# Sheet1.net
KiCad netlist of a schematic drawn in Altium Designer
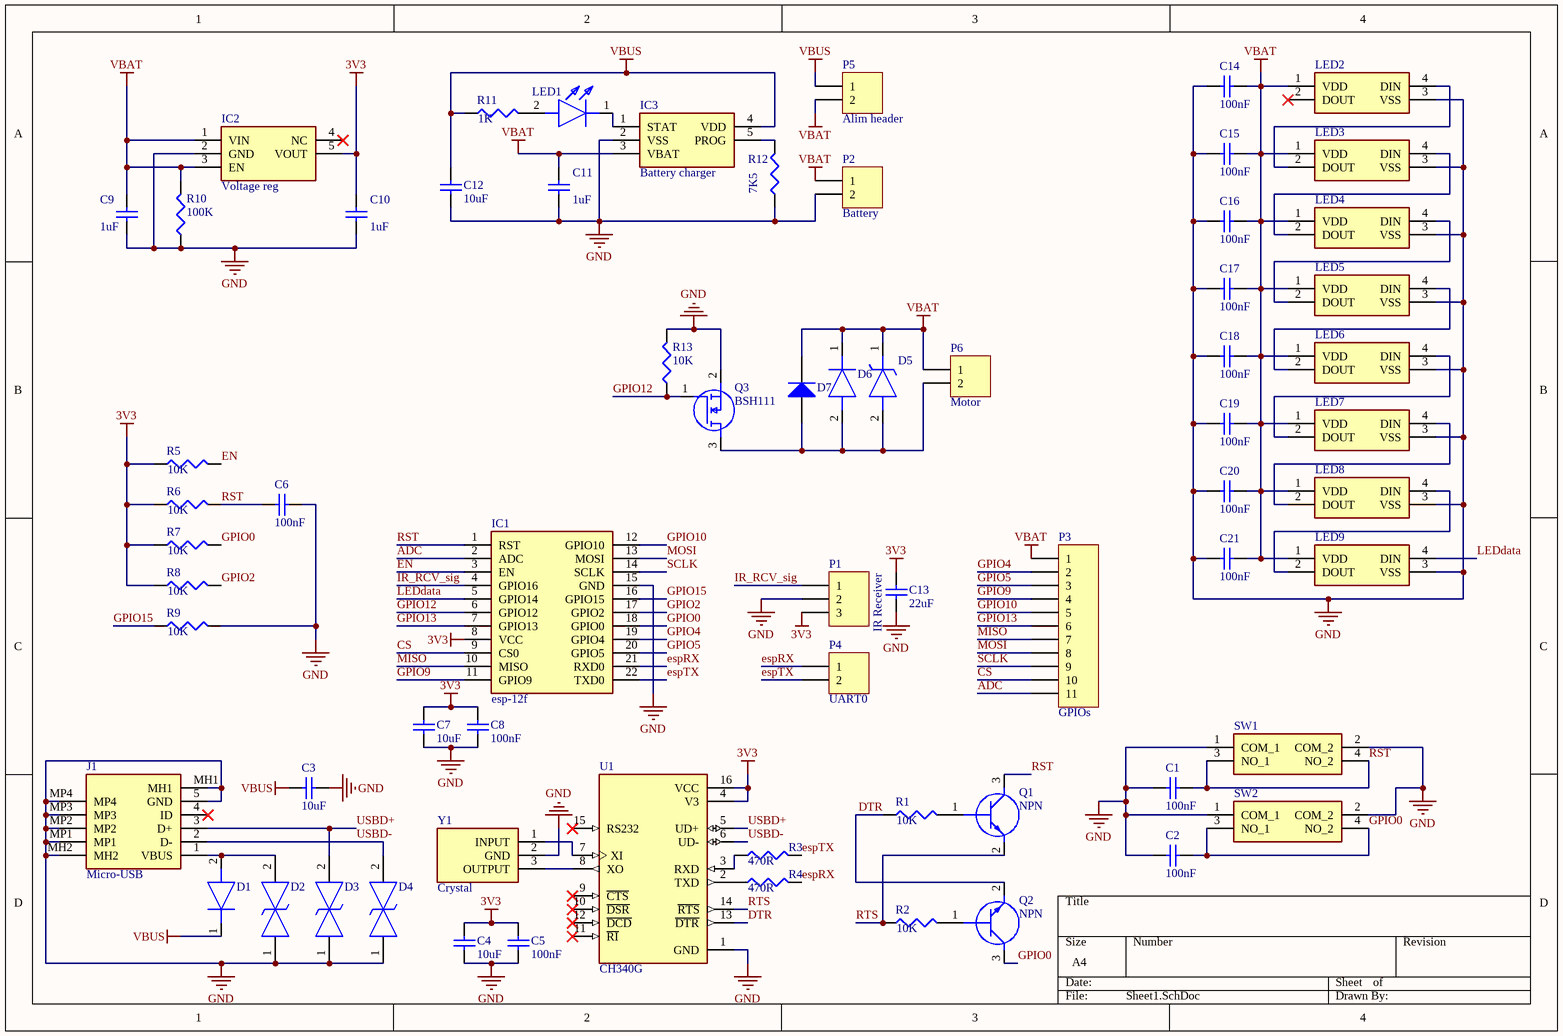
[diagram p0: Sheet1.SchDoc]

(export (version "E")
  (design (tool "Eeschema 10.0.6"))
  (components
    (comp (ref "C1")
      (value "100nF")
      (footprint "1608[0603]")
      (description "Capacitor (Semiconductor SIM Model)")
      (fields (field (name "Comment") "Cap Semi") (field (name "PUBLISHER") "Altium Limited"))
      (libsource (lib "Miscellaneous Devices") (part "Cap Semi"))
    )
    (comp (ref "C2")
      (value "100nF")
      (footprint "1608[0603]")
      (description "Capacitor (Semiconductor SIM Model)")
      (fields (field (name "Comment") "Cap Semi") (field (name "PUBLISHER") "Altium Limited"))
      (libsource (lib "Miscellaneous Devices") (part "Cap Semi"))
    )
    (comp (ref "C3")
      (value "10uF")
      (footprint "1608[0603]")
      (description "Capacitor (Semiconductor SIM Model)")
      (fields (field (name "Comment") "Cap Semi") (field (name "PUBLISHER") "Altium Limited"))
      (libsource (lib "Miscellaneous Devices") (part "Cap Semi"))
    )
    (comp (ref "C4")
      (value "10uF")
      (footprint "1608[0603]")
      (description "Capacitor (Semiconductor SIM Model)")
      (fields (field (name "Comment") "Cap Semi") (field (name "PUBLISHER") "Altium Limited"))
      (libsource (lib "Miscellaneous Devices") (part "Cap Semi"))
    )
    (comp (ref "C5")
      (value "100nF")
      (footprint "1608[0603]")
      (description "Capacitor (Semiconductor SIM Model)")
      (fields (field (name "Comment") "Cap Semi") (field (name "PUBLISHER") "Altium Limited"))
      (libsource (lib "Miscellaneous Devices") (part "Cap Semi"))
    )
    (comp (ref "C6")
      (value "100nF")
      (footprint "1608[0603]")
      (description "Capacitor (Semiconductor SIM Model)")
      (fields (field (name "Comment") "Cap Semi") (field (name "PUBLISHER") "Altium Limited"))
      (libsource (lib "Miscellaneous Devices") (part "Cap Semi"))
    )
    (comp (ref "C7")
      (value "10uF")
      (footprint "1608[0603]")
      (description "Capacitor (Semiconductor SIM Model)")
      (fields (field (name "Comment") "Cap Semi") (field (name "PUBLISHER") "Altium Limited"))
      (libsource (lib "Miscellaneous Devices") (part "Cap Semi"))
    )
    (comp (ref "C8")
      (value "100nF")
      (footprint "1608[0603]")
      (description "Capacitor (Semiconductor SIM Model)")
      (fields (field (name "Comment") "Cap Semi") (field (name "PUBLISHER") "Altium Limited"))
      (libsource (lib "Miscellaneous Devices") (part "Cap Semi"))
    )
    (comp (ref "C9")
      (value "1uF")
      (footprint "1608[0603]")
      (description "Capacitor (Semiconductor SIM Model)")
      (fields (field (name "Comment") "Cap Semi") (field (name "PUBLISHER") "Altium Limited"))
      (libsource (lib "Miscellaneous Devices") (part "Cap Semi"))
    )
    (comp (ref "C10")
      (value "1uF")
      (footprint "1608[0603]")
      (description "Capacitor (Semiconductor SIM Model)")
      (fields (field (name "Comment") "Cap Semi") (field (name "PUBLISHER") "Altium Limited"))
      (libsource (lib "Miscellaneous Devices") (part "Cap Semi"))
    )
    (comp (ref "C11")
      (value "1uF")
      (footprint "1608[0603]")
      (description "Capacitor (Semiconductor SIM Model)")
      (fields (field (name "Comment") "Cap Semi") (field (name "PUBLISHER") "Altium Limited"))
      (libsource (lib "Miscellaneous Devices") (part "Cap Semi"))
    )
    (comp (ref "C12")
      (value "10uF")
      (footprint "1608[0603]")
      (description "Capacitor (Semiconductor SIM Model)")
      (fields (field (name "Comment") "Cap Semi") (field (name "PUBLISHER") "Altium Limited"))
      (libsource (lib "Miscellaneous Devices") (part "Cap Semi"))
    )
    (comp (ref "C13")
      (value "22uF")
      (footprint "1608[0603]")
      (description "Capacitor (Semiconductor SIM Model)")
      (fields (field (name "Comment") "Cap Semi") (field (name "PUBLISHER") "Altium Limited"))
      (libsource (lib "Miscellaneous Devices") (part "Cap Semi"))
    )
    (comp (ref "C14")
      (value "100nF")
      (footprint "1608[0603]")
      (description "Capacitor (Semiconductor SIM Model)")
      (fields (field (name "Comment") "Cap Semi") (field (name "PUBLISHER") "Altium Limited"))
      (libsource (lib "Miscellaneous Devices") (part "Cap Semi"))
    )
    (comp (ref "C15")
      (value "100nF")
      (footprint "1608[0603]")
      (description "Capacitor (Semiconductor SIM Model)")
      (fields (field (name "Comment") "Cap Semi") (field (name "PUBLISHER") "Altium Limited"))
      (libsource (lib "Miscellaneous Devices") (part "Cap Semi"))
    )
    (comp (ref "C16")
      (value "100nF")
      (footprint "1608[0603]")
      (description "Capacitor (Semiconductor SIM Model)")
      (fields (field (name "Comment") "Cap Semi") (field (name "PUBLISHER") "Altium Limited"))
      (libsource (lib "Miscellaneous Devices") (part "Cap Semi"))
    )
    (comp (ref "C17")
      (value "100nF")
      (footprint "1608[0603]")
      (description "Capacitor (Semiconductor SIM Model)")
      (fields (field (name "Comment") "Cap Semi") (field (name "PUBLISHER") "Altium Limited"))
      (libsource (lib "Miscellaneous Devices") (part "Cap Semi"))
    )
    (comp (ref "C18")
      (value "100nF")
      (footprint "1608[0603]")
      (description "Capacitor (Semiconductor SIM Model)")
      (fields (field (name "Comment") "Cap Semi") (field (name "PUBLISHER") "Altium Limited"))
      (libsource (lib "Miscellaneous Devices") (part "Cap Semi"))
    )
    (comp (ref "C19")
      (value "100nF")
      (footprint "1608[0603]")
      (description "Capacitor (Semiconductor SIM Model)")
      (fields (field (name "Comment") "Cap Semi") (field (name "PUBLISHER") "Altium Limited"))
      (libsource (lib "Miscellaneous Devices") (part "Cap Semi"))
    )
    (comp (ref "C20")
      (value "100nF")
      (footprint "1608[0603]")
      (description "Capacitor (Semiconductor SIM Model)")
      (fields (field (name "Comment") "Cap Semi") (field (name "PUBLISHER") "Altium Limited"))
      (libsource (lib "Miscellaneous Devices") (part "Cap Semi"))
    )
    (comp (ref "C21")
      (value "100nF")
      (footprint "1608[0603]")
      (description "Capacitor (Semiconductor SIM Model)")
      (fields (field (name "Comment") "Cap Semi") (field (name "PUBLISHER") "Altium Limited"))
      (libsource (lib "Miscellaneous Devices") (part "Cap Semi"))
    )
    (comp (ref "D1")
      (value "1N5819HW-7-F")
      (footprint "SamacSys:SOD3716X145N")
      (description "Diode")
      (fields (field (name "MOUSER PART NUMBER") "621-1N5819HW-F"))
      (libsource (lib "*") (part "1N5819HW-7-F"))
    )
    (comp (ref "D2")
      (value "DF2B6M4CT,L3F")
      (footprint "SamacSys:DF2B6M4CTL3F")
      (description "TVS Diode (Bi-directional)")
      (fields (field (name "MOUSER PART NUMBER") "757-DF2B6M4CTL3F"))
      (libsource (lib "*") (part "DF2B6M4CT,L3F"))
    )
    (comp (ref "D3")
      (value "DF2B6M4CT,L3F")
      (footprint "SamacSys:DF2B6M4CTL3F")
      (description "TVS Diode (Bi-directional)")
      (fields (field (name "MOUSER PART NUMBER") "757-DF2B6M4CTL3F"))
      (libsource (lib "*") (part "DF2B6M4CT,L3F"))
    )
    (comp (ref "D4")
      (value "DF2B6M4CT,L3F")
      (footprint "SamacSys:DF2B6M4CTL3F")
      (description "TVS Diode (Bi-directional)")
      (fields (field (name "MOUSER PART NUMBER") "757-DF2B6M4CTL3F"))
      (libsource (lib "*") (part "DF2B6M4CT,L3F"))
    )
    (comp (ref "D5")
      (value "BZY55C30_RBG")
      (footprint "SamacSys:DIOC2012X85N")
      (description "Zener Diode")
      (fields
        (field (name "MANUFACTURER_PART_NUMBER") "BZY55C30 RBG")
        (field (name "MOUSER PART NUMBER") "821-BZY55C30RBG")
      )
      (libsource (lib "*") (part "BZY55C30_RBG"))
    )
    (comp (ref "D6")
      (value "PESD0603-240")
      (footprint "SamacSys:DIONC1608X55N")
      (description "Diode")
      (fields (field (name "MOUSER PART NUMBER") "650-PESD0603-240"))
      (libsource (lib "SamacSys") (part "PESD0603-240"))
    )
    (comp (ref "D7")
      (value "Diode 1N914")
      (footprint "DO-35")
      (description "High Conductance Fast Diode")
      (fields (field (name "PUBLISHER") "Altium Limited"))
      (libsource (lib "Miscellaneous Devices") (part "Diode 1N914"))
    )
    (comp (ref "IC1")
      (value "esp-12f")
      (footprint "SamacSys:esp12f")
      (description "Integrated Circuit")
      (libsource (lib "*") (part "esp-12f"))
    )
    (comp (ref "IC2")
      (value "Voltage reg")
      (footprint "SamacSys:SOT94P279X130-5N")
      (description "Integrated Circuit")
      (fields (field (name "MANUFACTURER_PART_NUMBER") "RT9013-12PB"))
      (libsource (lib "*") (part "RT9013-12PB"))
    )
    (comp (ref "IC3")
      (value "Battery charger")
      (footprint "SamacSys:SOT95P270X145-5N")
      (description "Integrated Circuit")
      (fields
        (field (name "MANUFACTURER_PART_NUMBER") "MCP73831T-2ACI/OT")
        (field (name "MOUSER PART NUMBER") "579-MCP73831T-2ACIOT")
      )
      (libsource (lib "*") (part "MCP73831T-2ACI_OT"))
    )
    (comp (ref "J1")
      (value "Micro-USB")
      (footprint "SamacSys:1051640001")
      (description "Connector")
      (fields
        (field (name "MANUFACTURER_PART_NUMBER") "105164-0001")
        (field (name "MOUSER PART NUMBER") "538-105164-0001")
      )
      (libsource (lib "*") (part "105164-0001"))
    )
    (comp (ref "LED1")
      (value "150060GS55040")
      (footprint "SamacSys:LEDC1608X50N")
      (description "LED")
      (fields (field (name "MOUSER PART NUMBER") "710-150060GS55040"))
      (libsource (lib "SamacSys") (part "150060GS55040"))
    )
    (comp (ref "LED2")
      (value "COM-13667")
      (footprint "SamacSys:COM13667")
      (description "LED")
      (fields (field (name "MOUSER PART NUMBER") "474-COM-13667"))
      (libsource (lib "SamacSys") (part "COM-13667"))
    )
    (comp (ref "LED3")
      (value "COM-13667")
      (footprint "SamacSys:COM13667")
      (description "LED")
      (fields (field (name "MOUSER PART NUMBER") "474-COM-13667"))
      (libsource (lib "SamacSys") (part "COM-13667"))
    )
    (comp (ref "LED4")
      (value "COM-13667")
      (footprint "SamacSys:COM13667")
      (description "LED")
      (fields (field (name "MOUSER PART NUMBER") "474-COM-13667"))
      (libsource (lib "SamacSys") (part "COM-13667"))
    )
    (comp (ref "LED5")
      (value "COM-13667")
      (footprint "SamacSys:COM13667")
      (description "LED")
      (fields (field (name "MOUSER PART NUMBER") "474-COM-13667"))
      (libsource (lib "SamacSys") (part "COM-13667"))
    )
    (comp (ref "LED6")
      (value "COM-13667")
      (footprint "SamacSys:COM13667")
      (description "LED")
      (fields (field (name "MOUSER PART NUMBER") "474-COM-13667"))
      (libsource (lib "SamacSys") (part "COM-13667"))
    )
    (comp (ref "LED7")
      (value "COM-13667")
      (footprint "SamacSys:COM13667")
      (description "LED")
      (fields (field (name "MOUSER PART NUMBER") "474-COM-13667"))
      (libsource (lib "SamacSys") (part "COM-13667"))
    )
    (comp (ref "LED8")
      (value "COM-13667")
      (footprint "SamacSys:COM13667")
      (description "LED")
      (fields (field (name "MOUSER PART NUMBER") "474-COM-13667"))
      (libsource (lib "SamacSys") (part "COM-13667"))
    )
    (comp (ref "LED9")
      (value "COM-13667")
      (footprint "SamacSys:COM13667")
      (description "LED")
      (fields (field (name "MOUSER PART NUMBER") "474-COM-13667"))
      (libsource (lib "SamacSys") (part "COM-13667"))
    )
    (comp (ref "P1")
      (value "IR Receiver")
      (footprint "HDR1X3")
      (description "Header, 3-Pin")
      (fields (field (name "PUBLISHER") "Altium Limited"))
      (libsource (lib "Miscellaneous Connectors") (part "Header 3"))
    )
    (comp (ref "P2")
      (value "Battery")
      (footprint "HDR1X2")
      (description "Header, 2-Pin")
      (fields (field (name "PUBLISHER") "Altium Limited"))
      (libsource (lib "Miscellaneous Connectors") (part "Header 2"))
    )
    (comp (ref "P3")
      (value "GPIOs")
      (footprint "HDR1X11")
      (description "Header, 11-Pin")
      (fields (field (name "PUBLISHER") "Altium Limited"))
      (libsource (lib "Miscellaneous Connectors") (part "Header 11"))
    )
    (comp (ref "P4")
      (value "UART0")
      (footprint "HDR1X2")
      (fields (field (name "PUBLISHER") "Altium Limited"))
      (libsource (lib "Miscellaneous Connectors") (part "Header 2"))
    )
    (comp (ref "P5")
      (value "Alim header")
      (footprint "HDR1X2")
      (description "Header, 2-Pin")
      (fields (field (name "PUBLISHER") "Altium Limited"))
      (libsource (lib "Miscellaneous Connectors") (part "Header 2"))
    )
    (comp (ref "P6")
      (value "Motor")
      (footprint "HDR1X2")
      (description "Header, 2-Pin")
      (fields (field (name "PUBLISHER") "Altium Limited"))
      (libsource (lib "Miscellaneous Connectors") (part "Header 2"))
    )
    (comp (ref "Q1")
      (value "NPN")
      (footprint "SamacSys:SOT95P230X110-3N")
      (description "Transistor BJT NPN")
      (fields
        (field (name "MANUFACTURER_PART_NUMBER") "BCW66FR")
        (field (name "MOUSER PART NUMBER") "771-BCW66FR")
      )
      (libsource (lib "*") (part "BCW66FR"))
    )
    (comp (ref "Q2")
      (value "NPN")
      (footprint "SamacSys:SOT95P230X110-3N")
      (description "Transistor BJT NPN")
      (fields
        (field (name "MANUFACTURER_PART_NUMBER") "BCW66FR")
        (field (name "MOUSER PART NUMBER") "771-BCW66FR")
      )
      (libsource (lib "*") (part "BCW66FR"))
    )
    (comp (ref "Q3")
      (value "BSH111")
      (footprint "SamacSys:SOT95P230X100-3N")
      (description "MOSFET (N-Channel)")
      (fields
        (field (name "MANUFACTURER_PART_NUMBER") "PMV15ENER")
        (field (name "MOUSER PART NUMBER") "771-PMV15ENER")
      )
      (libsource (lib "*") (part "PMV15ENER"))
    )
    (comp (ref "R1")
      (value "10K")
      (footprint "J1-0603")
      (description "Resistor")
      (fields (field (name "Comment") "Res3") (field (name "PUBLISHER") "Altium Limited"))
      (libsource (lib "Miscellaneous Devices") (part "Res3"))
    )
    (comp (ref "R2")
      (value "10K")
      (footprint "J1-0603")
      (description "Resistor")
      (fields (field (name "Comment") "Res3") (field (name "PUBLISHER") "Altium Limited"))
      (libsource (lib "Miscellaneous Devices") (part "Res3"))
    )
    (comp (ref "R3")
      (value "470R")
      (footprint "J1-0603")
      (description "Resistor")
      (fields (field (name "Comment") "Res3") (field (name "PUBLISHER") "Altium Limited"))
      (libsource (lib "Miscellaneous Devices") (part "Res3"))
    )
    (comp (ref "R4")
      (value "470R")
      (footprint "J1-0603")
      (description "Resistor")
      (fields (field (name "Comment") "Res3") (field (name "PUBLISHER") "Altium Limited"))
      (libsource (lib "Miscellaneous Devices") (part "Res3"))
    )
    (comp (ref "R5")
      (value "10K")
      (footprint "J1-0603")
      (description "Resistor")
      (fields (field (name "Comment") "Res3") (field (name "PUBLISHER") "Altium Limited"))
      (libsource (lib "Miscellaneous Devices") (part "Res3"))
    )
    (comp (ref "R6")
      (value "10K")
      (footprint "J1-0603")
      (description "Resistor")
      (fields (field (name "Comment") "Res3") (field (name "PUBLISHER") "Altium Limited"))
      (libsource (lib "Miscellaneous Devices") (part "Res3"))
    )
    (comp (ref "R7")
      (value "10K")
      (footprint "J1-0603")
      (description "Resistor")
      (fields (field (name "Comment") "Res3") (field (name "PUBLISHER") "Altium Limited"))
      (libsource (lib "Miscellaneous Devices") (part "Res3"))
    )
    (comp (ref "R8")
      (value "10K")
      (footprint "J1-0603")
      (description "Resistor")
      (fields (field (name "Comment") "Res3") (field (name "PUBLISHER") "Altium Limited"))
      (libsource (lib "Miscellaneous Devices") (part "Res3"))
    )
    (comp (ref "R9")
      (value "10K")
      (footprint "J1-0603")
      (description "Resistor")
      (fields (field (name "Comment") "Res3") (field (name "PUBLISHER") "Altium Limited"))
      (libsource (lib "Miscellaneous Devices") (part "Res3"))
    )
    (comp (ref "R10")
      (value "100K")
      (footprint "J1-0603")
      (description "Resistor")
      (fields (field (name "Comment") "Res3") (field (name "PUBLISHER") "Altium Limited"))
      (libsource (lib "Miscellaneous Devices") (part "Res3"))
    )
    (comp (ref "R11")
      (value "1K")
      (footprint "J1-0603")
      (description "Resistor")
      (fields (field (name "Comment") "Res3") (field (name "PUBLISHER") "Altium Limited"))
      (libsource (lib "Miscellaneous Devices") (part "Res3"))
    )
    (comp (ref "R12")
      (value "7K5")
      (footprint "J1-0603")
      (description "Resistor")
      (fields (field (name "Comment") "Res3") (field (name "PUBLISHER") "Altium Limited"))
      (libsource (lib "Miscellaneous Devices") (part "Res3"))
    )
    (comp (ref "R13")
      (value "10K")
      (footprint "J1-0603")
      (description "Resistor")
      (fields (field (name "Comment") "Res3") (field (name "PUBLISHER") "Altium Limited"))
      (libsource (lib "Miscellaneous Devices") (part "Res3"))
    )
    (comp (ref "SW1")
      (value "PTS526_SM15_SMTR2_LFS")
      (footprint "SamacSys:PTS526SM15SMTR2LFS")
      (description "Switch")
      (fields
        (field (name "MANUFACTURER_PART_NUMBER") "PTS526 SM15 SMTR2 LFS")
        (field (name "MOUSER PART NUMBER") "611-PTS526SM15SMTR2L")
      )
      (libsource (lib "SamacSys") (part "PTS526_SM15_SMTR2_LFS"))
    )
    (comp (ref "SW2")
      (value "PTS526_SM15_SMTR2_LFS")
      (footprint "SamacSys:PTS526SM15SMTR2LFS")
      (description "Switch")
      (fields
        (field (name "MANUFACTURER_PART_NUMBER") "PTS526 SM15 SMTR2 LFS")
        (field (name "MOUSER PART NUMBER") "611-PTS526SM15SMTR2L")
      )
      (libsource (lib "SamacSys") (part "PTS526_SM15_SMTR2_LFS"))
    )
    (comp (ref "U1")
      (value "CH340G")
      (footprint "SOIC127P600X180-16N")
      (description "USB Interface Integrated Circuit")
      (fields (field (name "MP") "Ch340G") (field (name "MF") "WCH"))
      (libsource (lib "CH340G") (part "CH340G"))
    )
    (comp (ref "Y1")
      (value "Crystal")
      (footprint "SamacSys:CSTCE12M0G55R0")
      (description "Crystal or Oscillator")
      (fields
        (field (name "MANUFACTURER_PART_NUMBER") "CSTCE12M0G55-R0")
        (field (name "MOUSER PART NUMBER") "81-CSTCE12M0G55-R0")
      )
      (libsource (lib "*") (part "CSTCE12M0G55-R0"))
    )
  )
  (nets
    (net (code "1") (name "/ADC") (class "Default")
      (node (ref "IC1") (pin "2") (pinfunction "ADC_2") (pintype "passive"))
      (node (ref "P3") (pin "11") (pinfunction "11_11") (pintype "passive"))
    )
    (net (code "2") (name "/CS") (class "Default")
      (node (ref "IC1") (pin "9") (pinfunction "CS0_9") (pintype "passive"))
      (node (ref "P3") (pin "10") (pinfunction "10_10") (pintype "passive"))
    )
    (net (code "3") (name "/DTR") (class "Default")
      (node (ref "Q2") (pin "2") (pinfunction "E_2") (pintype "passive"))
      (node (ref "R1") (pin "1") (pinfunction "1_1") (pintype "passive"))
      (node (ref "U1") (pin "13") (pinfunction "~{DTR}_13") (pintype "output"))
    )
    (net (code "4") (name "/EN") (class "Default")
      (node (ref "IC1") (pin "3") (pinfunction "EN_3") (pintype "passive"))
      (node (ref "R5") (pin "2") (pinfunction "2_2") (pintype "passive"))
    )
    (net (code "5") (name "/GPIO0") (class "Default")
      (node (ref "C2") (pin "1") (pinfunction "1_1") (pintype "passive"))
      (node (ref "IC1") (pin "18") (pinfunction "GPIO0_18") (pintype "passive"))
      (node (ref "Q2") (pin "3") (pinfunction "C_3") (pintype "passive"))
      (node (ref "R7") (pin "2") (pinfunction "2_2") (pintype "passive"))
      (node (ref "SW2") (pin "3") (pinfunction "NO_1_3") (pintype "passive"))
      (node (ref "SW2") (pin "4") (pinfunction "NO_2_4") (pintype "passive"))
    )
    (net (code "6") (name "/GPIO2") (class "Default")
      (node (ref "IC1") (pin "17") (pinfunction "GPIO2_17") (pintype "passive"))
      (node (ref "R8") (pin "2") (pinfunction "2_2") (pintype "passive"))
    )
    (net (code "7") (name "/GPIO4") (class "Default")
      (node (ref "IC1") (pin "19") (pinfunction "GPIO4_19") (pintype "passive"))
      (node (ref "P3") (pin "2") (pinfunction "2_2") (pintype "passive"))
    )
    (net (code "8") (name "/GPIO5") (class "Default")
      (node (ref "IC1") (pin "20") (pinfunction "GPIO5_20") (pintype "passive"))
      (node (ref "P3") (pin "3") (pinfunction "3_3") (pintype "passive"))
    )
    (net (code "9") (name "/GPIO9") (class "Default")
      (node (ref "IC1") (pin "11") (pinfunction "GPIO9_11") (pintype "passive"))
      (node (ref "P3") (pin "4") (pinfunction "4_4") (pintype "passive"))
    )
    (net (code "10") (name "/GPIO10") (class "Default")
      (node (ref "IC1") (pin "12") (pinfunction "GPIO10_12") (pintype "passive"))
      (node (ref "P3") (pin "5") (pinfunction "5_5") (pintype "passive"))
    )
    (net (code "11") (name "/GPIO12") (class "Default")
      (node (ref "IC1") (pin "6") (pinfunction "GPIO12_6") (pintype "passive"))
      (node (ref "Q3") (pin "1") (pinfunction "G_1") (pintype "passive"))
      (node (ref "R13") (pin "2") (pinfunction "2_2") (pintype "passive"))
    )
    (net (code "12") (name "/GPIO13") (class "Default")
      (node (ref "IC1") (pin "7") (pinfunction "GPIO13_7") (pintype "passive"))
      (node (ref "P3") (pin "6") (pinfunction "6_6") (pintype "passive"))
    )
    (net (code "13") (name "/GPIO15") (class "Default")
      (node (ref "IC1") (pin "16") (pinfunction "GPIO15_16") (pintype "passive"))
      (node (ref "R9") (pin "1") (pinfunction "1_1") (pintype "passive"))
    )
    (net (code "14") (name "/IR_RCV_sig") (class "Default")
      (node (ref "IC1") (pin "4") (pinfunction "GPIO16_4") (pintype "passive"))
      (node (ref "P1") (pin "1") (pinfunction "1_1") (pintype "passive"))
    )
    (net (code "15") (name "/LEDdata") (class "Default")
      (node (ref "IC1") (pin "5") (pinfunction "GPIO14_5") (pintype "passive"))
      (node (ref "LED9") (pin "4") (pinfunction "DIN_4") (pintype "passive"))
    )
    (net (code "16") (name "/MISO") (class "Default")
      (node (ref "IC1") (pin "10") (pinfunction "MISO_10") (pintype "passive"))
      (node (ref "P3") (pin "7") (pinfunction "7_7") (pintype "passive"))
    )
    (net (code "17") (name "/MOSI") (class "Default")
      (node (ref "IC1") (pin "13") (pinfunction "MOSI_13") (pintype "passive"))
      (node (ref "P3") (pin "8") (pinfunction "8_8") (pintype "passive"))
    )
    (net (code "18") (name "/RST") (class "Default")
      (node (ref "C1") (pin "1") (pinfunction "1_1") (pintype "passive"))
      (node (ref "C6") (pin "1") (pinfunction "1_1") (pintype "passive"))
      (node (ref "IC1") (pin "1") (pinfunction "RST_1") (pintype "passive"))
      (node (ref "Q1") (pin "3") (pinfunction "C_3") (pintype "passive"))
      (node (ref "R6") (pin "2") (pinfunction "2_2") (pintype "passive"))
      (node (ref "SW1") (pin "3") (pinfunction "NO_1_3") (pintype "passive"))
      (node (ref "SW1") (pin "4") (pinfunction "NO_2_4") (pintype "passive"))
    )
    (net (code "19") (name "/RTS") (class "Default")
      (node (ref "Q1") (pin "2") (pinfunction "E_2") (pintype "passive"))
      (node (ref "R2") (pin "1") (pinfunction "1_1") (pintype "passive"))
      (node (ref "U1") (pin "14") (pinfunction "~{RTS}_14") (pintype "output"))
    )
    (net (code "20") (name "/SCLK") (class "Default")
      (node (ref "IC1") (pin "14") (pinfunction "SCLK_14") (pintype "passive"))
      (node (ref "P3") (pin "9") (pinfunction "9_9") (pintype "passive"))
    )
    (net (code "21") (name "/USBD+") (class "Default")
      (node (ref "D3") (pin "2") (pinfunction "2_2") (pintype "passive"))
      (node (ref "J1") (pin "3") (pinfunction "D+_3") (pintype "passive"))
      (node (ref "U1") (pin "5") (pinfunction "UD+_5") (pintype "bidirectional"))
    )
    (net (code "22") (name "/USBD-") (class "Default")
      (node (ref "D4") (pin "2") (pinfunction "2_2") (pintype "passive"))
      (node (ref "J1") (pin "2") (pinfunction "D-_2") (pintype "passive"))
      (node (ref "U1") (pin "6") (pinfunction "UD-_6") (pintype "bidirectional"))
    )
    (net (code "23") (name "/espRX") (class "Default")
      (node (ref "IC1") (pin "21") (pinfunction "RXD0_21") (pintype "passive"))
      (node (ref "P4") (pin "1") (pinfunction "1_1") (pintype "passive"))
      (node (ref "R4") (pin "2") (pinfunction "2_2") (pintype "passive"))
    )
    (net (code "24") (name "/espTX") (class "Default")
      (node (ref "IC1") (pin "22") (pinfunction "TXD0_22") (pintype "passive"))
      (node (ref "P4") (pin "2") (pinfunction "2_2") (pintype "passive"))
      (node (ref "R3") (pin "2") (pinfunction "2_2") (pintype "passive"))
    )
    (net (code "25") (name "3V3") (class "Default")
      (node (ref "C10") (pin "1") (pinfunction "1_1") (pintype "passive"))
      (node (ref "C13") (pin "1") (pinfunction "1_1") (pintype "passive"))
      (node (ref "C4") (pin "1") (pinfunction "1_1") (pintype "passive"))
      (node (ref "C5") (pin "1") (pinfunction "1_1") (pintype "passive"))
      (node (ref "C7") (pin "1") (pinfunction "1_1") (pintype "passive"))
      (node (ref "C8") (pin "1") (pinfunction "1_1") (pintype "passive"))
      (node (ref "IC1") (pin "8") (pinfunction "VCC_8") (pintype "passive"))
      (node (ref "IC2") (pin "5") (pinfunction "VOUT_5") (pintype "passive"))
      (node (ref "P1") (pin "3") (pinfunction "3_3") (pintype "passive"))
      (node (ref "R5") (pin "1") (pinfunction "1_1") (pintype "passive"))
      (node (ref "R6") (pin "1") (pinfunction "1_1") (pintype "passive"))
      (node (ref "R7") (pin "1") (pinfunction "1_1") (pintype "passive"))
      (node (ref "R8") (pin "1") (pinfunction "1_1") (pintype "passive"))
      (node (ref "U1") (pin "16") (pinfunction "VCC_16") (pintype "power_in"))
      (node (ref "U1") (pin "4") (pinfunction "V3_4") (pintype "power_in"))
    )
    (net (code "26") (name "GND") (class "Default")
      (node (ref "C1") (pin "2") (pinfunction "2_2") (pintype "passive"))
      (node (ref "C10") (pin "2") (pinfunction "2_2") (pintype "passive"))
      (node (ref "C11") (pin "2") (pinfunction "2_2") (pintype "passive"))
      (node (ref "C12") (pin "2") (pinfunction "2_2") (pintype "passive"))
      (node (ref "C13") (pin "2") (pinfunction "2_2") (pintype "passive"))
      (node (ref "C14") (pin "1") (pinfunction "1_1") (pintype "passive"))
      (node (ref "C15") (pin "1") (pinfunction "1_1") (pintype "passive"))
      (node (ref "C16") (pin "1") (pinfunction "1_1") (pintype "passive"))
      (node (ref "C17") (pin "1") (pinfunction "1_1") (pintype "passive"))
      (node (ref "C18") (pin "1") (pinfunction "1_1") (pintype "passive"))
      (node (ref "C19") (pin "1") (pinfunction "1_1") (pintype "passive"))
      (node (ref "C2") (pin "2") (pinfunction "2_2") (pintype "passive"))
      (node (ref "C20") (pin "1") (pinfunction "1_1") (pintype "passive"))
      (node (ref "C21") (pin "1") (pinfunction "1_1") (pintype "passive"))
      (node (ref "C3") (pin "1") (pinfunction "1_1") (pintype "passive"))
      (node (ref "C4") (pin "2") (pinfunction "2_2") (pintype "passive"))
      (node (ref "C5") (pin "2") (pinfunction "2_2") (pintype "passive"))
      (node (ref "C6") (pin "2") (pinfunction "2_2") (pintype "passive"))
      (node (ref "C7") (pin "2") (pinfunction "2_2") (pintype "passive"))
      (node (ref "C8") (pin "2") (pinfunction "2_2") (pintype "passive"))
      (node (ref "C9") (pin "2") (pinfunction "2_2") (pintype "passive"))
      (node (ref "D2") (pin "1") (pinfunction "1_1") (pintype "passive"))
      (node (ref "D3") (pin "1") (pinfunction "1_1") (pintype "passive"))
      (node (ref "D4") (pin "1") (pinfunction "1_1") (pintype "passive"))
      (node (ref "IC1") (pin "15") (pinfunction "GND_15") (pintype "passive"))
      (node (ref "IC2") (pin "2") (pinfunction "GND_2") (pintype "passive"))
      (node (ref "IC3") (pin "2") (pinfunction "VSS_2") (pintype "passive"))
      (node (ref "J1") (pin "5") (pinfunction "GND_5") (pintype "passive"))
      (node (ref "J1") (pin "MH1") (pinfunction "MH1_MH1") (pintype "passive"))
      (node (ref "J1") (pin "MH2") (pinfunction "MH2_MH2") (pintype "passive"))
      (node (ref "J1") (pin "MP1") (pinfunction "MP1_MP1") (pintype "passive"))
      (node (ref "J1") (pin "MP2") (pinfunction "MP2_MP2") (pintype "passive"))
      (node (ref "J1") (pin "MP3") (pinfunction "MP3_MP3") (pintype "passive"))
      (node (ref "J1") (pin "MP4") (pinfunction "MP4_MP4") (pintype "passive"))
      (node (ref "LED2") (pin "3") (pinfunction "VSS_3") (pintype "passive"))
      (node (ref "LED3") (pin "3") (pinfunction "VSS_3") (pintype "passive"))
      (node (ref "LED4") (pin "3") (pinfunction "VSS_3") (pintype "passive"))
      (node (ref "LED5") (pin "3") (pinfunction "VSS_3") (pintype "passive"))
      (node (ref "LED6") (pin "3") (pinfunction "VSS_3") (pintype "passive"))
      (node (ref "LED7") (pin "3") (pinfunction "VSS_3") (pintype "passive"))
      (node (ref "LED8") (pin "3") (pinfunction "VSS_3") (pintype "passive"))
      (node (ref "LED9") (pin "3") (pinfunction "VSS_3") (pintype "passive"))
      (node (ref "P1") (pin "2") (pinfunction "2_2") (pintype "passive"))
      (node (ref "P2") (pin "2") (pinfunction "2_2") (pintype "passive"))
      (node (ref "Q3") (pin "2") (pinfunction "S_2") (pintype "passive"))
      (node (ref "R10") (pin "1") (pinfunction "1_1") (pintype "passive"))
      (node (ref "R12") (pin "1") (pinfunction "1_1") (pintype "passive"))
      (node (ref "R13") (pin "1") (pinfunction "1_1") (pintype "passive"))
      (node (ref "R9") (pin "2") (pinfunction "2_2") (pintype "passive"))
      (node (ref "SW1") (pin "1") (pinfunction "COM_1_1") (pintype "passive"))
      (node (ref "SW1") (pin "2") (pinfunction "COM_2_2") (pintype "passive"))
      (node (ref "SW2") (pin "1") (pinfunction "COM_1_1") (pintype "passive"))
      (node (ref "SW2") (pin "2") (pinfunction "COM_2_2") (pintype "passive"))
      (node (ref "U1") (pin "1") (pinfunction "GND_1") (pintype "power_in"))
      (node (ref "Y1") (pin "2") (pinfunction "GND_2") (pintype "passive"))
    )
    (net (code "27") (name "Net-(D1-A)") (class "Default")
      (node (ref "D1") (pin "2") (pinfunction "A_2") (pintype "passive"))
      (node (ref "D2") (pin "2") (pinfunction "2_2") (pintype "passive"))
      (node (ref "J1") (pin "1") (pinfunction "VBUS_1") (pintype "passive"))
    )
    (net (code "28") (name "Net-(D5-A)") (class "Default")
      (node (ref "D5") (pin "2") (pinfunction "A_2") (pintype "passive"))
      (node (ref "D6") (pin "2") (pinfunction "A_2") (pintype "passive"))
      (node (ref "D7") (pin "1") (pinfunction "A_1") (pintype "passive"))
      (node (ref "P6") (pin "2") (pinfunction "2_2") (pintype "passive"))
      (node (ref "Q3") (pin "3") (pinfunction "D_3") (pintype "passive"))
    )
    (net (code "29") (name "Net-(IC3-PROG)") (class "Default")
      (node (ref "IC3") (pin "5") (pinfunction "PROG_5") (pintype "passive"))
      (node (ref "R12") (pin "2") (pinfunction "2_2") (pintype "passive"))
    )
    (net (code "30") (name "Net-(IC3-STAT)") (class "Default")
      (node (ref "IC3") (pin "1") (pinfunction "STAT_1") (pintype "passive"))
      (node (ref "LED1") (pin "1") (pinfunction "K_1") (pintype "passive"))
    )
    (net (code "31") (name "Net-(LED1-A)") (class "Default")
      (node (ref "LED1") (pin "2") (pinfunction "A_2") (pintype "passive"))
      (node (ref "R11") (pin "2") (pinfunction "2_2") (pintype "passive"))
    )
    (net (code "32") (name "Net-(LED2-DIN)") (class "Default")
      (node (ref "LED2") (pin "4") (pinfunction "DIN_4") (pintype "passive"))
      (node (ref "LED3") (pin "2") (pinfunction "DOUT_2") (pintype "passive"))
    )
    (net (code "33") (name "Net-(LED3-DIN)") (class "Default")
      (node (ref "LED3") (pin "4") (pinfunction "DIN_4") (pintype "passive"))
      (node (ref "LED4") (pin "2") (pinfunction "DOUT_2") (pintype "passive"))
    )
    (net (code "34") (name "Net-(LED4-DIN)") (class "Default")
      (node (ref "LED4") (pin "4") (pinfunction "DIN_4") (pintype "passive"))
      (node (ref "LED5") (pin "2") (pinfunction "DOUT_2") (pintype "passive"))
    )
    (net (code "35") (name "Net-(LED5-DIN)") (class "Default")
      (node (ref "LED5") (pin "4") (pinfunction "DIN_4") (pintype "passive"))
      (node (ref "LED6") (pin "2") (pinfunction "DOUT_2") (pintype "passive"))
    )
    (net (code "36") (name "Net-(LED6-DIN)") (class "Default")
      (node (ref "LED6") (pin "4") (pinfunction "DIN_4") (pintype "passive"))
      (node (ref "LED7") (pin "2") (pinfunction "DOUT_2") (pintype "passive"))
    )
    (net (code "37") (name "Net-(LED7-DIN)") (class "Default")
      (node (ref "LED7") (pin "4") (pinfunction "DIN_4") (pintype "passive"))
      (node (ref "LED8") (pin "2") (pinfunction "DOUT_2") (pintype "passive"))
    )
    (net (code "38") (name "Net-(LED8-DIN)") (class "Default")
      (node (ref "LED8") (pin "4") (pinfunction "DIN_4") (pintype "passive"))
      (node (ref "LED9") (pin "2") (pinfunction "DOUT_2") (pintype "passive"))
    )
    (net (code "39") (name "Net-(Q1-B)") (class "Default")
      (node (ref "Q1") (pin "1") (pinfunction "B_1") (pintype "passive"))
      (node (ref "R1") (pin "2") (pinfunction "2_2") (pintype "passive"))
    )
    (net (code "40") (name "Net-(Q2-B)") (class "Default")
      (node (ref "Q2") (pin "1") (pinfunction "B_1") (pintype "passive"))
      (node (ref "R2") (pin "2") (pinfunction "2_2") (pintype "passive"))
    )
    (net (code "41") (name "Net-(U1-RXD)") (class "Default")
      (node (ref "R3") (pin "1") (pinfunction "1_1") (pintype "passive"))
      (node (ref "U1") (pin "3") (pinfunction "RXD_3") (pintype "input"))
    )
    (net (code "42") (name "Net-(U1-TXD)") (class "Default")
      (node (ref "R4") (pin "1") (pinfunction "1_1") (pintype "passive"))
      (node (ref "U1") (pin "2") (pinfunction "TXD_2") (pintype "output"))
    )
    (net (code "43") (name "Net-(U1-XI)") (class "Default")
      (node (ref "U1") (pin "7") (pinfunction "XI_7") (pintype "input"))
      (node (ref "Y1") (pin "1") (pinfunction "INPUT_1") (pintype "passive"))
    )
    (net (code "44") (name "Net-(U1-XO)") (class "Default")
      (node (ref "U1") (pin "8") (pinfunction "XO_8") (pintype "output"))
      (node (ref "Y1") (pin "3") (pinfunction "OUTPUT_3") (pintype "passive"))
    )
    (net (code "45") (name "VBAT") (class "Default")
      (node (ref "C11") (pin "1") (pinfunction "1_1") (pintype "passive"))
      (node (ref "C14") (pin "2") (pinfunction "2_2") (pintype "passive"))
      (node (ref "C15") (pin "2") (pinfunction "2_2") (pintype "passive"))
      (node (ref "C16") (pin "2") (pinfunction "2_2") (pintype "passive"))
      (node (ref "C17") (pin "2") (pinfunction "2_2") (pintype "passive"))
      (node (ref "C18") (pin "2") (pinfunction "2_2") (pintype "passive"))
      (node (ref "C19") (pin "2") (pinfunction "2_2") (pintype "passive"))
      (node (ref "C20") (pin "2") (pinfunction "2_2") (pintype "passive"))
      (node (ref "C21") (pin "2") (pinfunction "2_2") (pintype "passive"))
      (node (ref "C9") (pin "1") (pinfunction "1_1") (pintype "passive"))
      (node (ref "D5") (pin "1") (pinfunction "K_1") (pintype "passive"))
      (node (ref "D6") (pin "1") (pinfunction "K_1") (pintype "passive"))
      (node (ref "D7") (pin "2") (pinfunction "K_2") (pintype "passive"))
      (node (ref "IC2") (pin "1") (pinfunction "VIN_1") (pintype "passive"))
      (node (ref "IC2") (pin "3") (pinfunction "EN_3") (pintype "passive"))
      (node (ref "IC3") (pin "3") (pinfunction "VBAT_3") (pintype "passive"))
      (node (ref "LED2") (pin "1") (pinfunction "VDD_1") (pintype "passive"))
      (node (ref "LED3") (pin "1") (pinfunction "VDD_1") (pintype "passive"))
      (node (ref "LED4") (pin "1") (pinfunction "VDD_1") (pintype "passive"))
      (node (ref "LED5") (pin "1") (pinfunction "VDD_1") (pintype "passive"))
      (node (ref "LED6") (pin "1") (pinfunction "VDD_1") (pintype "passive"))
      (node (ref "LED7") (pin "1") (pinfunction "VDD_1") (pintype "passive"))
      (node (ref "LED8") (pin "1") (pinfunction "VDD_1") (pintype "passive"))
      (node (ref "LED9") (pin "1") (pinfunction "VDD_1") (pintype "passive"))
      (node (ref "P2") (pin "1") (pinfunction "1_1") (pintype "passive"))
      (node (ref "P3") (pin "1") (pinfunction "1_1") (pintype "passive"))
      (node (ref "P5") (pin "2") (pinfunction "2_2") (pintype "passive"))
      (node (ref "P6") (pin "1") (pinfunction "1_1") (pintype "passive"))
      (node (ref "R10") (pin "2") (pinfunction "2_2") (pintype "passive"))
    )
    (net (code "46") (name "VBUS") (class "Default")
      (node (ref "C12") (pin "1") (pinfunction "1_1") (pintype "passive"))
      (node (ref "C3") (pin "2") (pinfunction "2_2") (pintype "passive"))
      (node (ref "D1") (pin "1") (pinfunction "K_1") (pintype "passive"))
      (node (ref "IC3") (pin "4") (pinfunction "VDD_4") (pintype "passive"))
      (node (ref "P5") (pin "1") (pinfunction "1_1") (pintype "passive"))
      (node (ref "R11") (pin "1") (pinfunction "1_1") (pintype "passive"))
    )
    (net (code "47") (name "unconnected-(IC2-NC-Pad4)") (class "Default")
      (node (ref "IC2") (pin "4") (pinfunction "NC_4") (pintype "passive+no_connect"))
    )
    (net (code "48") (name "unconnected-(J1-ID-Pad4)") (class "Default")
      (node (ref "J1") (pin "4") (pinfunction "ID_4") (pintype "passive+no_connect"))
    )
    (net (code "49") (name "unconnected-(LED2-DOUT-Pad2)") (class "Default")
      (node (ref "LED2") (pin "2") (pinfunction "DOUT_2") (pintype "passive+no_connect"))
    )
    (net (code "50") (name "unconnected-(U1-RS232-Pad15)") (class "Default")
      (node (ref "U1") (pin "15") (pinfunction "RS232_15") (pintype "input+no_connect"))
    )
    (net (code "51") (name "unconnected-(U1-~{CTS}-Pad9)") (class "Default")
      (node (ref "U1") (pin "9") (pinfunction "~{CTS}_9") (pintype "input+no_connect"))
    )
    (net (code "52") (name "unconnected-(U1-~{DCD}-Pad12)") (class "Default")
      (node (ref "U1") (pin "12") (pinfunction "~{DCD}_12") (pintype "input+no_connect"))
    )
    (net (code "53") (name "unconnected-(U1-~{DSR}-Pad10)") (class "Default")
      (node (ref "U1") (pin "10") (pinfunction "~{DSR}_10") (pintype "input+no_connect"))
    )
    (net (code "54") (name "unconnected-(U1-~{RI}-Pad11)") (class "Default")
      (node (ref "U1") (pin "11") (pinfunction "~{RI}_11") (pintype "input+no_connect"))
    )
  )
)
